# proiect2025_v16_sch.net
KiCad netlist of a schematic drawn in EAGLE
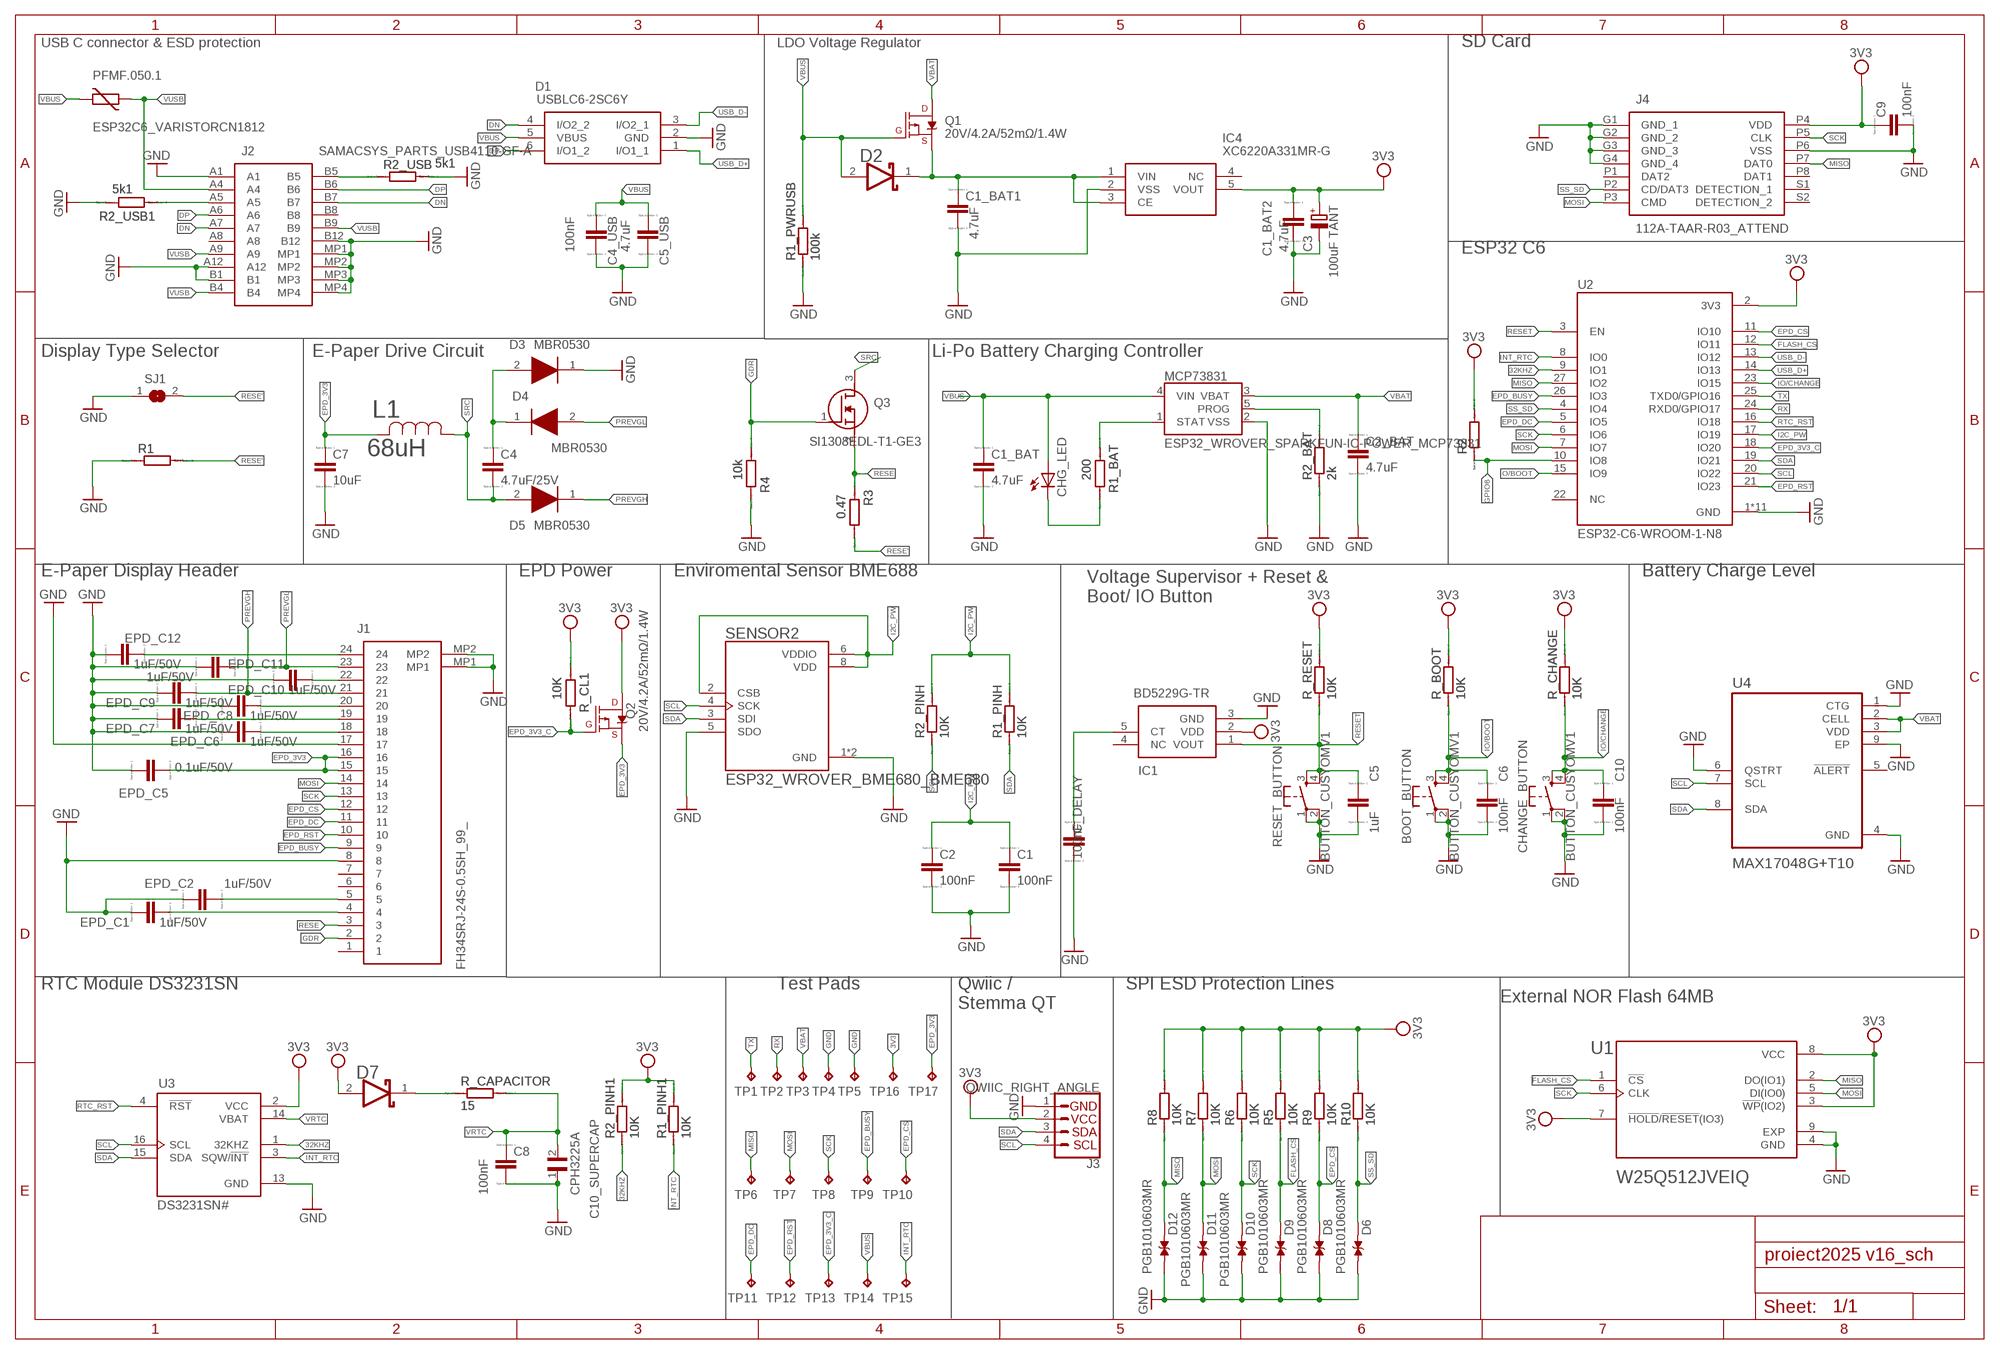
[diagram p0: schematic, sheet 1]

(export (version "E")
  (design (tool "Eeschema 10.0.6"))
  (components
    (comp (ref "BOOT_BUTTON")
      (value "BUTTON_CUSYOMV1")
      (footprint "eagle-import:MYBUTTON")
      (libsource (lib "eagle-import") (part "BUTTON_CUSYOMV1"))
    )
    (comp (ref "C1")
      (value "100nF")
      (footprint "eagle-import:EAGLE-LTSPICE_C0402")
      (libsource (lib "eagle-import") (part "EAGLE-LTSPICE_CC0402"))
    )
    (comp (ref "C1_BAT")
      (value "4.7uF")
      (footprint "eagle-import:EAGLE-LTSPICE_C0402")
      (libsource (lib "eagle-import") (part "EAGLE-LTSPICE_CC0402"))
    )
    (comp (ref "C1_BAT1")
      (value "4.7uF")
      (footprint "eagle-import:EAGLE-LTSPICE_C0402")
      (libsource (lib "eagle-import") (part "EAGLE-LTSPICE_CC0402"))
    )
    (comp (ref "C1_BAT2")
      (value "4.7uF")
      (footprint "eagle-import:EAGLE-LTSPICE_C0402")
      (libsource (lib "eagle-import") (part "EAGLE-LTSPICE_CC0402"))
    )
    (comp (ref "C2")
      (value "100nF")
      (footprint "eagle-import:EAGLE-LTSPICE_C0402")
      (libsource (lib "eagle-import") (part "EAGLE-LTSPICE_CC0402"))
    )
    (comp (ref "C2_BAT")
      (value "4.7uF")
      (footprint "eagle-import:EAGLE-LTSPICE_C0402")
      (libsource (lib "eagle-import") (part "EAGLE-LTSPICE_CC0402"))
    )
    (comp (ref "C3")
      (value "100uF TANT")
      (footprint "eagle-import:RCL_CT3528")
      (libsource (lib "eagle-import") (part "RCL_CPOL-EUCT3528"))
    )
    (comp (ref "C4")
      (value "4.7uF/25V")
      (footprint "eagle-import:EAGLE-LTSPICE_C0402")
      (libsource (lib "eagle-import") (part "EAGLE-LTSPICE_CC0402"))
    )
    (comp (ref "C4_USB")
      (value "100nF")
      (footprint "eagle-import:EAGLE-LTSPICE_C0402")
      (libsource (lib "eagle-import") (part "EAGLE-LTSPICE_CC0402"))
    )
    (comp (ref "C5")
      (value "1uF")
      (footprint "eagle-import:EAGLE-LTSPICE_C0402")
      (libsource (lib "eagle-import") (part "EAGLE-LTSPICE_CC0402"))
    )
    (comp (ref "C5_USB")
      (value "4.7uF")
      (footprint "eagle-import:EAGLE-LTSPICE_C0402")
      (libsource (lib "eagle-import") (part "EAGLE-LTSPICE_CC0402"))
    )
    (comp (ref "C6")
      (value "100nF")
      (footprint "eagle-import:EAGLE-LTSPICE_C0402")
      (libsource (lib "eagle-import") (part "EAGLE-LTSPICE_CC0402"))
    )
    (comp (ref "C7")
      (value "10uF")
      (footprint "eagle-import:EAGLE-LTSPICE_C0402")
      (libsource (lib "eagle-import") (part "EAGLE-LTSPICE_CC0402"))
    )
    (comp (ref "C8")
      (value "100nF")
      (footprint "eagle-import:EAGLE-LTSPICE_C0402")
      (libsource (lib "eagle-import") (part "EAGLE-LTSPICE_CC0402"))
    )
    (comp (ref "C9")
      (value "100nF")
      (footprint "eagle-import:EAGLE-LTSPICE_C0402")
      (libsource (lib "eagle-import") (part "EAGLE-LTSPICE_CC0402"))
    )
    (comp (ref "C10")
      (value "100nF")
      (footprint "eagle-import:EAGLE-LTSPICE_C0402")
      (libsource (lib "eagle-import") (part "EAGLE-LTSPICE_CC0402"))
    )
    (comp (ref "C10_SUPERCAP")
      (value "CPH3225A")
      (footprint "eagle-import:CAPCP3225X100N")
      (fields (field (name "MF") "Seiko Instruments"))
      (libsource (lib "eagle-import") (part "CPH3225A"))
    )
    (comp (ref "CHANGE_BUTTON")
      (value "BUTTON_CUSYOMV1")
      (footprint "eagle-import:MYBUTTON")
      (libsource (lib "eagle-import") (part "BUTTON_CUSYOMV1"))
    )
    (comp (ref "CHG_LED")
      (value "ADAFRUIT_LEDCHIP-LED0603")
      (footprint "eagle-import:ADAFRUIT_CHIP-LED0603")
      (libsource (lib "eagle-import") (part "ADAFRUIT_LEDCHIP-LED0603"))
    )
    (comp (ref "C_DELAY")
      (value "100nF")
      (footprint "eagle-import:EAGLE-LTSPICE_C0402")
      (libsource (lib "eagle-import") (part "EAGLE-LTSPICE_CC0402"))
    )
    (comp (ref "D1")
      (value "USBLC6-2SC6Y")
      (footprint "eagle-import:SOT95P280X145-6N")
      (fields (field (name "MF") "STMicroelectronics"))
      (libsource (lib "eagle-import") (part "USBLC6-2SC6Y"))
    )
    (comp (ref "D2")
      (value "ESP32_WROVER_AVX---SD0805S020S1R0_AVX_SD0805S020S1R0_0_0AVX_SD0805S020S1R0_0_0")
      (footprint "eagle-import:ESP32_WROVER_AVX---SD0805S020S1R0_AVX_SD0805S020S1R0_0")
      (fields
        (field (name "DIGIKEY_PART_NUMBER") "478-7800-1-ND")
        (field (name "MF") "AVX")
        (field (name "MOUSER_PART_NUMBER") "581-SD0805S020S1R0")
      )
      (libsource (lib "eagle-import") (part "ESP32_WROVER_AVX---SD0805S020S1R0_AVX_SD0805S020S1R0_0_0AVX_SD0805S020S1R0_0_0"))
    )
    (comp (ref "D3")
      (value "MBR0530")
      (footprint "eagle-import:SOD3716X135N")
      (fields (field (name "MF") "ON Semiconductor"))
      (libsource (lib "eagle-import") (part "MBR0530"))
    )
    (comp (ref "D4")
      (value "MBR0530")
      (footprint "eagle-import:SOD3716X135N")
      (fields (field (name "MF") "ON Semiconductor"))
      (libsource (lib "eagle-import") (part "MBR0530"))
    )
    (comp (ref "D5")
      (value "MBR0530")
      (footprint "eagle-import:SOD3716X135N")
      (fields (field (name "MF") "ON Semiconductor"))
      (libsource (lib "eagle-import") (part "MBR0530"))
    )
    (comp (ref "D6")
      (value "PGB1010603MR")
      (footprint "eagle-import:DIOC1608X36N")
      (fields (field (name "MF") "Littelfuse Inc."))
      (libsource (lib "eagle-import") (part "PGB1010603MR"))
    )
    (comp (ref "D7")
      (value "ESP32_WROVER_AVX---SD0805S020S1R0_AVX_SD0805S020S1R0_0_0AVX_SD0805S020S1R0_0_0")
      (footprint "eagle-import:ESP32_WROVER_AVX---SD0805S020S1R0_AVX_SD0805S020S1R0_0")
      (fields
        (field (name "DIGIKEY_PART_NUMBER") "478-7800-1-ND")
        (field (name "MF") "AVX")
        (field (name "MOUSER_PART_NUMBER") "581-SD0805S020S1R0")
      )
      (libsource (lib "eagle-import") (part "ESP32_WROVER_AVX---SD0805S020S1R0_AVX_SD0805S020S1R0_0_0AVX_SD0805S020S1R0_0_0"))
    )
    (comp (ref "D8")
      (value "PGB1010603MR")
      (footprint "eagle-import:DIOC1608X36N")
      (fields (field (name "MF") "Littelfuse Inc."))
      (libsource (lib "eagle-import") (part "PGB1010603MR"))
    )
    (comp (ref "D9")
      (value "PGB1010603MR")
      (footprint "eagle-import:DIOC1608X36N")
      (fields (field (name "MF") "Littelfuse Inc."))
      (libsource (lib "eagle-import") (part "PGB1010603MR"))
    )
    (comp (ref "D10")
      (value "PGB1010603MR")
      (footprint "eagle-import:DIOC1608X36N")
      (fields (field (name "MF") "Littelfuse Inc."))
      (libsource (lib "eagle-import") (part "PGB1010603MR"))
    )
    (comp (ref "D11")
      (value "PGB1010603MR")
      (footprint "eagle-import:DIOC1608X36N")
      (fields (field (name "MF") "Littelfuse Inc."))
      (libsource (lib "eagle-import") (part "PGB1010603MR"))
    )
    (comp (ref "D12")
      (value "PGB1010603MR")
      (footprint "eagle-import:DIOC1608X36N")
      (fields (field (name "MF") "Littelfuse Inc."))
      (libsource (lib "eagle-import") (part "PGB1010603MR"))
    )
    (comp (ref "EPD_C1")
      (value "1uF/50V")
      (footprint "eagle-import:EAGLE-LTSPICE_C0402")
      (libsource (lib "eagle-import") (part "EAGLE-LTSPICE_CC0402"))
    )
    (comp (ref "EPD_C2")
      (value "1uF/50V")
      (footprint "eagle-import:EAGLE-LTSPICE_C0402")
      (libsource (lib "eagle-import") (part "EAGLE-LTSPICE_CC0402"))
    )
    (comp (ref "EPD_C5")
      (value "0.1uF/50V")
      (footprint "eagle-import:EAGLE-LTSPICE_C0402")
      (libsource (lib "eagle-import") (part "EAGLE-LTSPICE_CC0402"))
    )
    (comp (ref "EPD_C6")
      (value "1uF/50V")
      (footprint "eagle-import:EAGLE-LTSPICE_C0402")
      (libsource (lib "eagle-import") (part "EAGLE-LTSPICE_CC0402"))
    )
    (comp (ref "EPD_C7")
      (value "1uF/50V")
      (footprint "eagle-import:EAGLE-LTSPICE_C0402")
      (libsource (lib "eagle-import") (part "EAGLE-LTSPICE_CC0402"))
    )
    (comp (ref "EPD_C8")
      (value "1uF/50V")
      (footprint "eagle-import:EAGLE-LTSPICE_C0402")
      (libsource (lib "eagle-import") (part "EAGLE-LTSPICE_CC0402"))
    )
    (comp (ref "EPD_C9")
      (value "1uF/50V")
      (footprint "eagle-import:EAGLE-LTSPICE_C0402")
      (libsource (lib "eagle-import") (part "EAGLE-LTSPICE_CC0402"))
    )
    (comp (ref "EPD_C10")
      (value "1uF/50V")
      (footprint "eagle-import:EAGLE-LTSPICE_C0402")
      (libsource (lib "eagle-import") (part "EAGLE-LTSPICE_CC0402"))
    )
    (comp (ref "EPD_C11")
      (value "1uF/50V")
      (footprint "eagle-import:EAGLE-LTSPICE_C0402")
      (libsource (lib "eagle-import") (part "EAGLE-LTSPICE_CC0402"))
    )
    (comp (ref "EPD_C12")
      (value "1uF/50V")
      (footprint "eagle-import:EAGLE-LTSPICE_C0402")
      (libsource (lib "eagle-import") (part "EAGLE-LTSPICE_CC0402"))
    )
    (comp (ref "IC1")
      (value "BD5229G-TR")
      (footprint "eagle-import:SOT95P280X125-5N")
      (fields (field (name "MOUSER_PART_NUMBER") "755-BD5229G-TR"))
      (libsource (lib "eagle-import") (part "BD5229G-TR"))
    )
    (comp (ref "IC4")
      (value "XC6220A331MR-G")
      (footprint "eagle-import:SOT95P280X120-5N")
      (fields (field (name "MOUSER_PART_NUMBER") "865-XC6220A331MR-G"))
      (libsource (lib "eagle-import") (part "XC6220A331MR-G"))
    )
    (comp (ref "J1")
      (value "FH34SRJ-24S-0.5SH_99_")
      (footprint "eagle-import:FH34SRJ24S05SH99")
      (fields
        (field (name "MANUFACTURER_PART_NUMBER") "FH34SRJ-24S-0.5SH(99)")
        (field (name "MOUSER_PART_NUMBER") "798-FH34SRJ24S05SH99")
      )
      (libsource (lib "eagle-import") (part "FH34SRJ-24S-0.5SH_99_"))
    )
    (comp (ref "J2")
      (value "SAMACSYS_PARTS_USB4110-GF-A")
      (footprint "eagle-import:SAMACSYS_PARTS_USB4110GFA")
      (fields
        (field (name "MANUFACTURER_PART_NUMBER") "USB4110-GF-A")
        (field (name "MOUSER_PART_NUMBER") "640-USB4110-GF-A")
      )
      (libsource (lib "eagle-import") (part "SAMACSYS_PARTS_USB4110-GF-A"))
    )
    (comp (ref "J3")
      (value "QWIIC_RIGHT_ANGLE")
      (footprint "eagle-import:JST04_1MM_RA")
      (libsource (lib "eagle-import") (part "QWIIC_CONNECTORJS-1MM"))
    )
    (comp (ref "J4")
      (value "112A-TAAR-R03_ATTEND")
      (footprint "eagle-import:112ATAARR03ATTEND")
      (fields (field (name "MANUFACTURER_PART_NUMBER") "112A-TAAR-R03 ATTEND"))
      (libsource (lib "eagle-import") (part "112A-TAAR-R03_ATTEND"))
    )
    (comp (ref "L1")
      (value "68uH")
      (footprint "eagle-import:IND_4828-WE-TPC_WRE")
      (fields
        (field (name "MANUFACTURER_PART_NUMBER") "744043680")
        (field (name "COPYRIGHT") "Copyright (C) 2024 Ultra Librarian. All rights reserved.")
      )
      (libsource (lib "eagle-import") (part "744043680IND_4828-WE-TPC_WRE"))
    )
    (comp (ref "MCP73831")
      (value "ESP32_WROVER_SPARKFUN-IC-POWER_MCP73831")
      (footprint "eagle-import:ESP32_WROVER_SPARKFUN-IC-POWER_SOT23-5")
      (libsource (lib "eagle-import") (part "ESP32_WROVER_SPARKFUN-IC-POWER_MCP73831"))
    )
    (comp (ref "PFMF.050.1")
      (value "ESP32C6_VARISTORCN1812")
      (footprint "eagle-import:ESP32C6_VARISTOR_CT_CN1812")
      (libsource (lib "eagle-import") (part "ESP32C6_VARISTORCN1812"))
    )
    (comp (ref "Q1")
      (value "20V/4.2A/52mΩ/1.4W")
      (footprint "eagle-import:ESP32_WROVER_SPARKFUN-DISCRETESEMI_SOT23-3")
      (libsource (lib "eagle-import") (part "ESP32_WROVER_SPARKFUN-DISCRETESEMI_MOSFET_PCH-DMG2305UX-7"))
    )
    (comp (ref "Q2")
      (value "20V/4.2A/52mΩ/1.4W")
      (footprint "eagle-import:ESP32_WROVER_SPARKFUN-DISCRETESEMI_SOT23-3")
      (libsource (lib "eagle-import") (part "ESP32_WROVER_SPARKFUN-DISCRETESEMI_MOSFET_PCH-DMG2305UX-7"))
    )
    (comp (ref "Q3")
      (value "SI1308EDL-T1-GE3")
      (footprint "eagle-import:SOT65P210X110-3N")
      (fields (field (name "MF") "Vishay Siliconix"))
      (libsource (lib "eagle-import") (part "SI1308EDL-T1-GE3"))
    )
    (comp (ref "R1")
      (value "ESP32_WROVER_EAGLE-LTSPICE_RR0402")
      (footprint "eagle-import:ESP32_WROVER_EAGLE-LTSPICE_R0402")
      (libsource (lib "eagle-import") (part "ESP32_WROVER_EAGLE-LTSPICE_RR0402"))
    )
    (comp (ref "R1_BAT")
      (value "200")
      (footprint "eagle-import:ESP32_WROVER_EAGLE-LTSPICE_R0402")
      (libsource (lib "eagle-import") (part "ESP32_WROVER_EAGLE-LTSPICE_RR0402"))
    )
    (comp (ref "R1_PINH")
      (value "10K")
      (footprint "eagle-import:ESP32_WROVER_EAGLE-LTSPICE_R0402")
      (libsource (lib "eagle-import") (part "ESP32_WROVER_EAGLE-LTSPICE_RR0402"))
    )
    (comp (ref "R1_PINH1")
      (value "10K")
      (footprint "eagle-import:ESP32_WROVER_EAGLE-LTSPICE_R0402")
      (libsource (lib "eagle-import") (part "ESP32_WROVER_EAGLE-LTSPICE_RR0402"))
    )
    (comp (ref "R1_PWRUSB")
      (value "100k")
      (footprint "eagle-import:ESP32_WROVER_EAGLE-LTSPICE_R0402")
      (libsource (lib "eagle-import") (part "ESP32_WROVER_EAGLE-LTSPICE_RR0402"))
    )
    (comp (ref "R2")
      (value "ESP32_WROVER_EAGLE-LTSPICE_RR0402")
      (footprint "eagle-import:ESP32_WROVER_EAGLE-LTSPICE_R0402")
      (libsource (lib "eagle-import") (part "ESP32_WROVER_EAGLE-LTSPICE_RR0402"))
    )
    (comp (ref "R2_BAT")
      (value "2k")
      (footprint "eagle-import:ESP32_WROVER_EAGLE-LTSPICE_R0402")
      (libsource (lib "eagle-import") (part "ESP32_WROVER_EAGLE-LTSPICE_RR0402"))
    )
    (comp (ref "R2_PINH")
      (value "10K")
      (footprint "eagle-import:ESP32_WROVER_EAGLE-LTSPICE_R0402")
      (libsource (lib "eagle-import") (part "ESP32_WROVER_EAGLE-LTSPICE_RR0402"))
    )
    (comp (ref "R2_PINH1")
      (value "10K")
      (footprint "eagle-import:ESP32_WROVER_EAGLE-LTSPICE_R0402")
      (libsource (lib "eagle-import") (part "ESP32_WROVER_EAGLE-LTSPICE_RR0402"))
    )
    (comp (ref "R2_USB")
      (value "5k1")
      (footprint "eagle-import:ESP32_WROVER_EAGLE-LTSPICE_R0402")
      (libsource (lib "eagle-import") (part "ESP32_WROVER_EAGLE-LTSPICE_RR0402"))
    )
    (comp (ref "R2_USB1")
      (value "5k1")
      (footprint "eagle-import:ESP32_WROVER_EAGLE-LTSPICE_R0402")
      (libsource (lib "eagle-import") (part "ESP32_WROVER_EAGLE-LTSPICE_RR0402"))
    )
    (comp (ref "R3")
      (value "0.47")
      (footprint "eagle-import:ESP32_WROVER_EAGLE-LTSPICE_R0402")
      (libsource (lib "eagle-import") (part "ESP32_WROVER_EAGLE-LTSPICE_RR0402"))
    )
    (comp (ref "R4")
      (value "10k")
      (footprint "eagle-import:ESP32_WROVER_EAGLE-LTSPICE_R0402")
      (libsource (lib "eagle-import") (part "ESP32_WROVER_EAGLE-LTSPICE_RR0402"))
    )
    (comp (ref "R5")
      (value "10K")
      (footprint "eagle-import:ESP32_WROVER_EAGLE-LTSPICE_R0402")
      (libsource (lib "eagle-import") (part "ESP32_WROVER_EAGLE-LTSPICE_RR0402"))
    )
    (comp (ref "R6")
      (value "10K")
      (footprint "eagle-import:ESP32_WROVER_EAGLE-LTSPICE_R0402")
      (libsource (lib "eagle-import") (part "ESP32_WROVER_EAGLE-LTSPICE_RR0402"))
    )
    (comp (ref "R7")
      (value "10K")
      (footprint "eagle-import:ESP32_WROVER_EAGLE-LTSPICE_R0402")
      (libsource (lib "eagle-import") (part "ESP32_WROVER_EAGLE-LTSPICE_RR0402"))
    )
    (comp (ref "R8")
      (value "10K")
      (footprint "eagle-import:ESP32_WROVER_EAGLE-LTSPICE_R0402")
      (libsource (lib "eagle-import") (part "ESP32_WROVER_EAGLE-LTSPICE_RR0402"))
    )
    (comp (ref "R9")
      (value "10K")
      (footprint "eagle-import:ESP32_WROVER_EAGLE-LTSPICE_R0402")
      (libsource (lib "eagle-import") (part "ESP32_WROVER_EAGLE-LTSPICE_RR0402"))
    )
    (comp (ref "R10")
      (value "10K")
      (footprint "eagle-import:ESP32_WROVER_EAGLE-LTSPICE_R0402")
      (libsource (lib "eagle-import") (part "ESP32_WROVER_EAGLE-LTSPICE_RR0402"))
    )
    (comp (ref "RESET_BUTTON")
      (value "BUTTON_CUSYOMV1")
      (footprint "eagle-import:MYBUTTON")
      (libsource (lib "eagle-import") (part "BUTTON_CUSYOMV1"))
    )
    (comp (ref "R_BOOT")
      (value "10K")
      (footprint "eagle-import:ESP32_WROVER_EAGLE-LTSPICE_R0402")
      (libsource (lib "eagle-import") (part "ESP32_WROVER_EAGLE-LTSPICE_RR0402"))
    )
    (comp (ref "R_CAPACITOR")
      (value "15")
      (footprint "eagle-import:ESP32_WROVER_EAGLE-LTSPICE_R0402")
      (libsource (lib "eagle-import") (part "ESP32_WROVER_EAGLE-LTSPICE_RR0402"))
    )
    (comp (ref "R_CHANGE")
      (value "10K")
      (footprint "eagle-import:ESP32_WROVER_EAGLE-LTSPICE_R0402")
      (libsource (lib "eagle-import") (part "ESP32_WROVER_EAGLE-LTSPICE_RR0402"))
    )
    (comp (ref "R_CL1")
      (value "10K")
      (footprint "eagle-import:ESP32_WROVER_EAGLE-LTSPICE_R0402")
      (libsource (lib "eagle-import") (part "ESP32_WROVER_EAGLE-LTSPICE_RR0402"))
    )
    (comp (ref "R_RESET")
      (value "10K")
      (footprint "eagle-import:ESP32_WROVER_EAGLE-LTSPICE_R0402")
      (libsource (lib "eagle-import") (part "ESP32_WROVER_EAGLE-LTSPICE_RR0402"))
    )
    (comp (ref "SENSOR2")
      (value "ESP32_WROVER_BME680_BME680")
      (footprint "eagle-import:ESP32_WROVER_BME680_PSON80P300X300X100-8N")
      (fields (field (name "MF") "Bosch Sensortec") (field (name "MP") "BME680"))
      (libsource (lib "eagle-import") (part "ESP32_WROVER_BME680_BME680"))
    )
    (comp (ref "SJ1") (value "SJ") (footprint "eagle-import:SJ") (libsource (lib "eagle-import") (part "SJ")))
    (comp (ref "TP1")
      (value "TPTP20R")
      (footprint "eagle-import:TP20R")
      (libsource (lib "eagle-import") (part "TPTP20R"))
    )
    (comp (ref "TP2")
      (value "TPTP20R")
      (footprint "eagle-import:TP20R")
      (libsource (lib "eagle-import") (part "TPTP20R"))
    )
    (comp (ref "TP3")
      (value "TPTP20R")
      (footprint "eagle-import:TP20R")
      (libsource (lib "eagle-import") (part "TPTP20R"))
    )
    (comp (ref "TP4")
      (value "TPTP20R")
      (footprint "eagle-import:TP20R")
      (libsource (lib "eagle-import") (part "TPTP20R"))
    )
    (comp (ref "TP5")
      (value "TPTP20R")
      (footprint "eagle-import:TP20R")
      (libsource (lib "eagle-import") (part "TPTP20R"))
    )
    (comp (ref "TP6")
      (value "TPTP20R")
      (footprint "eagle-import:TP20R")
      (libsource (lib "eagle-import") (part "TPTP20R"))
    )
    (comp (ref "TP7")
      (value "TPTP20R")
      (footprint "eagle-import:TP20R")
      (libsource (lib "eagle-import") (part "TPTP20R"))
    )
    (comp (ref "TP8")
      (value "TPTP20R")
      (footprint "eagle-import:TP20R")
      (libsource (lib "eagle-import") (part "TPTP20R"))
    )
    (comp (ref "TP9")
      (value "TPTP20R")
      (footprint "eagle-import:TP20R")
      (libsource (lib "eagle-import") (part "TPTP20R"))
    )
    (comp (ref "TP10")
      (value "TPTP20R")
      (footprint "eagle-import:TP20R")
      (libsource (lib "eagle-import") (part "TPTP20R"))
    )
    (comp (ref "TP11")
      (value "TPTP20R")
      (footprint "eagle-import:TP20R")
      (libsource (lib "eagle-import") (part "TPTP20R"))
    )
    (comp (ref "TP12")
      (value "TPTP20R")
      (footprint "eagle-import:TP20R")
      (libsource (lib "eagle-import") (part "TPTP20R"))
    )
    (comp (ref "TP13")
      (value "TPTP20R")
      (footprint "eagle-import:TP20R")
      (libsource (lib "eagle-import") (part "TPTP20R"))
    )
    (comp (ref "TP14")
      (value "TPTP20R")
      (footprint "eagle-import:TP20R")
      (libsource (lib "eagle-import") (part "TPTP20R"))
    )
    (comp (ref "TP15")
      (value "TPTP20R")
      (footprint "eagle-import:TP20R")
      (libsource (lib "eagle-import") (part "TPTP20R"))
    )
    (comp (ref "TP16")
      (value "TPTP20R")
      (footprint "eagle-import:TP20R")
      (libsource (lib "eagle-import") (part "TPTP20R"))
    )
    (comp (ref "TP17")
      (value "TPTP20R")
      (footprint "eagle-import:TP20R")
      (libsource (lib "eagle-import") (part "TPTP20R"))
    )
    (comp (ref "U1")
      (value "W25Q512JVEIQ")
      (footprint "eagle-import:SON127P600X800X80-9N")
      (fields (field (name "MF") "Winbond Electronics"))
      (libsource (lib "eagle-import") (part "W25Q512JVEIQ"))
    )
    (comp (ref "U2")
      (value "ESP32-C6-WROOM-1-N8")
      (footprint "eagle-import:XCVR_ESP32-C6-WROOM-1-N8")
      (fields (field (name "MF") "Espressif Systems"))
      (libsource (lib "eagle-import") (part "ESP32-C6-WROOM-1-N8"))
    )
    (comp (ref "U3")
      (value "DS3231SN#")
      (footprint "eagle-import:SOIC127P1032X265-16N")
      (fields (field (name "MF") "Analog Devices"))
      (libsource (lib "eagle-import") (part "DS3231SN#"))
    )
    (comp (ref "U4")
      (value "MAX17048G+T10")
      (footprint "eagle-import:SON50P200X200X80-9N")
      (fields (field (name "MF") "Analog Devices"))
      (libsource (lib "eagle-import") (part "MAX17048G+T10"))
    )
  )
  (nets
    (net (code "1") (name "3V3") (class "Default")
      (node (ref "C1_BAT2") (pin "1") (pinfunction "1_1") (pintype "passive"))
      (node (ref "C3") (pin "+") (pinfunction "+_+") (pintype "passive"))
      (node (ref "C9") (pin "1") (pinfunction "1_1") (pintype "passive"))
      (node (ref "D7") (pin "2") (pinfunction "ANODE_2") (pintype "bidirectional"))
      (node (ref "IC1") (pin "2") (pinfunction "VDD_2") (pintype "bidirectional"))
      (node (ref "IC4") (pin "5") (pinfunction "VOUT_5") (pintype "bidirectional"))
      (node (ref "J3") (pin "2") (pinfunction "2_2") (pintype "power_in"))
      (node (ref "J4") (pin "P4") (pinfunction "VDD_P4") (pintype "bidirectional"))
      (node (ref "Q2") (pin "3") (pinfunction "D_3") (pintype "bidirectional"))
      (node (ref "R10") (pin "2") (pinfunction "2_2") (pintype "passive"))
      (node (ref "R1_PINH1") (pin "2") (pinfunction "2_2") (pintype "passive"))
      (node (ref "R2") (pin "2") (pinfunction "2_2") (pintype "passive"))
      (node (ref "R2_PINH1") (pin "2") (pinfunction "2_2") (pintype "passive"))
      (node (ref "R5") (pin "2") (pinfunction "2_2") (pintype "passive"))
      (node (ref "R6") (pin "2") (pinfunction "2_2") (pintype "passive"))
      (node (ref "R7") (pin "2") (pinfunction "2_2") (pintype "passive"))
      (node (ref "R8") (pin "2") (pinfunction "2_2") (pintype "passive"))
      (node (ref "R9") (pin "2") (pinfunction "2_2") (pintype "passive"))
      (node (ref "R_BOOT") (pin "2") (pinfunction "2_2") (pintype "passive"))
      (node (ref "R_CHANGE") (pin "2") (pinfunction "2_2") (pintype "passive"))
      (node (ref "R_CL1") (pin "2") (pinfunction "2_2") (pintype "passive"))
      (node (ref "R_RESET") (pin "2") (pinfunction "2_2") (pintype "passive"))
      (node (ref "TP16") (pin "TP") (pinfunction "TP_TP") (pintype "input"))
      (node (ref "U1") (pin "3") (pinfunction "~{WP}(IO2)_3") (pintype "bidirectional"))
      (node (ref "U1") (pin "7") (pinfunction "~{HOLD}/~{RESET}(IO3)_7") (pintype "bidirectional"))
      (node (ref "U1") (pin "8") (pinfunction "VCC_8") (pintype "power_in"))
      (node (ref "U2") (pin "2") (pinfunction "3V3_2") (pintype "power_in"))
      (node (ref "U3") (pin "2") (pinfunction "VCC_2") (pintype "power_in"))
    )
    (net (code "2") (name "32KHZ") (class "Default")
      (node (ref "R2_PINH1") (pin "1") (pinfunction "1_1") (pintype "passive"))
      (node (ref "U2") (pin "9") (pinfunction "IO1_9") (pintype "bidirectional"))
      (node (ref "U3") (pin "1") (pinfunction "32KHZ_1") (pintype "output"))
    )
    (net (code "3") (name "DN") (class "Default")
      (node (ref "D1") (pin "4") (pinfunction "I/O2_2_4") (pintype "bidirectional"))
      (node (ref "J2") (pin "A7") (pinfunction "A7_A7") (pintype "bidirectional"))
      (node (ref "J2") (pin "B7") (pinfunction "B7_B7") (pintype "bidirectional"))
    )
    (net (code "4") (name "DP") (class "Default")
      (node (ref "D1") (pin "6") (pinfunction "I/O1_2_6") (pintype "bidirectional"))
      (node (ref "J2") (pin "A6") (pinfunction "A6_A6") (pintype "bidirectional"))
      (node (ref "J2") (pin "B6") (pinfunction "B6_B6") (pintype "bidirectional"))
    )
    (net (code "5") (name "EPD_3V3") (class "Default")
      (node (ref "C7") (pin "1") (pinfunction "1_1") (pintype "passive"))
      (node (ref "EPD_C5") (pin "2") (pinfunction "2_2") (pintype "passive"))
      (node (ref "J1") (pin "15") (pinfunction "15_15") (pintype "bidirectional"))
      (node (ref "J1") (pin "16") (pinfunction "16_16") (pintype "bidirectional"))
      (node (ref "L1") (pin "2") (pinfunction "2_2") (pintype "passive"))
      (node (ref "Q2") (pin "2") (pinfunction "S_2") (pintype "bidirectional"))
      (node (ref "TP17") (pin "TP") (pinfunction "TP_TP") (pintype "input"))
    )
    (net (code "6") (name "EPD_3V3_C") (class "Default")
      (node (ref "Q2") (pin "1") (pinfunction "G_1") (pintype "bidirectional"))
      (node (ref "R_CL1") (pin "1") (pinfunction "1_1") (pintype "passive"))
      (node (ref "TP13") (pin "TP") (pinfunction "TP_TP") (pintype "input"))
      (node (ref "U2") (pin "18") (pinfunction "IO20_18") (pintype "bidirectional"))
    )
    (net (code "7") (name "EPD_BUSY") (class "Default")
      (node (ref "J1") (pin "9") (pinfunction "9_9") (pintype "bidirectional"))
      (node (ref "TP9") (pin "TP") (pinfunction "TP_TP") (pintype "input"))
      (node (ref "U2") (pin "26") (pinfunction "IO3_26") (pintype "bidirectional"))
    )
    (net (code "8") (name "EPD_CS") (class "Default")
      (node (ref "D8") (pin "2") (pinfunction "2_2") (pintype "passive"))
      (node (ref "J1") (pin "12") (pinfunction "12_12") (pintype "bidirectional"))
      (node (ref "R9") (pin "1") (pinfunction "1_1") (pintype "passive"))
      (node (ref "TP10") (pin "TP") (pinfunction "TP_TP") (pintype "input"))
      (node (ref "U2") (pin "11") (pinfunction "IO10_11") (pintype "bidirectional"))
    )
    (net (code "9") (name "EPD_DC") (class "Default")
      (node (ref "J1") (pin "11") (pinfunction "11_11") (pintype "bidirectional"))
      (node (ref "TP11") (pin "TP") (pinfunction "TP_TP") (pintype "input"))
      (node (ref "U2") (pin "5") (pinfunction "IO5_5") (pintype "bidirectional"))
    )
    (net (code "10") (name "EPD_RST") (class "Default")
      (node (ref "J1") (pin "10") (pinfunction "10_10") (pintype "bidirectional"))
      (node (ref "TP12") (pin "TP") (pinfunction "TP_TP") (pintype "input"))
      (node (ref "U2") (pin "21") (pinfunction "IO23_21") (pintype "bidirectional"))
    )
    (net (code "11") (name "FLASH_CS") (class "Default")
      (node (ref "D9") (pin "2") (pinfunction "2_2") (pintype "passive"))
      (node (ref "R5") (pin "1") (pinfunction "1_1") (pintype "passive"))
      (node (ref "U1") (pin "1") (pinfunction "~{CS}_1") (pintype "input"))
      (node (ref "U2") (pin "12") (pinfunction "IO11_12") (pintype "bidirectional"))
    )
    (net (code "12") (name "GDR") (class "Default")
      (node (ref "J1") (pin "2") (pinfunction "2_2") (pintype "bidirectional"))
      (node (ref "Q3") (pin "1") (pinfunction "G_1") (pintype "bidirectional"))
      (node (ref "R4") (pin "2") (pinfunction "2_2") (pintype "passive"))
    )
    (net (code "13") (name "GND") (class "Default")
      (node (ref "BOOT_BUTTON") (pin "1") (pinfunction "1_1") (pintype "passive"))
      (node (ref "BOOT_BUTTON") (pin "2") (pinfunction "2_2") (pintype "passive"))
      (node (ref "C1") (pin "2") (pinfunction "2_2") (pintype "passive"))
      (node (ref "C10") (pin "2") (pinfunction "2_2") (pintype "passive"))
      (node (ref "C10_SUPERCAP") (pin "1") (pinfunction "1_1") (pintype "passive"))
      (node (ref "C1_BAT") (pin "2") (pinfunction "2_2") (pintype "passive"))
      (node (ref "C1_BAT1") (pin "2") (pinfunction "2_2") (pintype "passive"))
      (node (ref "C1_BAT2") (pin "2") (pinfunction "2_2") (pintype "passive"))
      (node (ref "C2") (pin "2") (pinfunction "2_2") (pintype "passive"))
      (node (ref "C2_BAT") (pin "2") (pinfunction "2_2") (pintype "passive"))
      (node (ref "C3") (pin "-") (pinfunction "-_-") (pintype "passive"))
      (node (ref "C4_USB") (pin "2") (pinfunction "2_2") (pintype "passive"))
      (node (ref "C5") (pin "2") (pinfunction "2_2") (pintype "passive"))
      (node (ref "C5_USB") (pin "2") (pinfunction "2_2") (pintype "passive"))
      (node (ref "C6") (pin "2") (pinfunction "2_2") (pintype "passive"))
      (node (ref "C7") (pin "2") (pinfunction "2_2") (pintype "passive"))
      (node (ref "C8") (pin "2") (pinfunction "2_2") (pintype "passive"))
      (node (ref "C9") (pin "2") (pinfunction "2_2") (pintype "passive"))
      (node (ref "CHANGE_BUTTON") (pin "1") (pinfunction "1_1") (pintype "passive"))
      (node (ref "CHANGE_BUTTON") (pin "2") (pinfunction "2_2") (pintype "passive"))
      (node (ref "C_DELAY") (pin "2") (pinfunction "2_2") (pintype "passive"))
      (node (ref "D1") (pin "2") (pinfunction "GND_2") (pintype "bidirectional"))
      (node (ref "D10") (pin "1") (pinfunction "1_1") (pintype "passive"))
      (node (ref "D11") (pin "1") (pinfunction "1_1") (pintype "passive"))
      (node (ref "D12") (pin "1") (pinfunction "1_1") (pintype "passive"))
      (node (ref "D3") (pin "1") (pinfunction "K_1") (pintype "bidirectional"))
      (node (ref "D6") (pin "1") (pinfunction "1_1") (pintype "passive"))
      (node (ref "D8") (pin "1") (pinfunction "1_1") (pintype "passive"))
      (node (ref "D9") (pin "1") (pinfunction "1_1") (pintype "passive"))
      (node (ref "EPD_C1") (pin "1") (pinfunction "1_1") (pintype "passive"))
      (node (ref "EPD_C10") (pin "1") (pinfunction "1_1") (pintype "passive"))
      (node (ref "EPD_C11") (pin "1") (pinfunction "1_1") (pintype "passive"))
      (node (ref "EPD_C12") (pin "1") (pinfunction "1_1") (pintype "passive"))
      (node (ref "EPD_C2") (pin "1") (pinfunction "1_1") (pintype "passive"))
      (node (ref "EPD_C5") (pin "1") (pinfunction "1_1") (pintype "passive"))
      (node (ref "EPD_C6") (pin "1") (pinfunction "1_1") (pintype "passive"))
      (node (ref "EPD_C7") (pin "1") (pinfunction "1_1") (pintype "passive"))
      (node (ref "EPD_C8") (pin "1") (pinfunction "1_1") (pintype "passive"))
      (node (ref "EPD_C9") (pin "1") (pinfunction "1_1") (pintype "passive"))
      (node (ref "IC1") (pin "3") (pinfunction "GND_3") (pintype "bidirectional"))
      (node (ref "IC4") (pin "2") (pinfunction "VSS_2") (pintype "bidirectional"))
      (node (ref "J1") (pin "17") (pinfunction "17_17") (pintype "bidirectional"))
      (node (ref "J1") (pin "8") (pinfunction "8_8") (pintype "bidirectional"))
      (node (ref "J1") (pin "MP1") (pinfunction "MP1_MP1") (pintype "bidirectional"))
      (node (ref "J1") (pin "MP2") (pinfunction "MP2_MP2") (pintype "bidirectional"))
      (node (ref "J2") (pin "A1") (pinfunction "A1_A1") (pintype "bidirectional"))
      (node (ref "J2") (pin "A12") (pinfunction "A12_A12") (pintype "bidirectional"))
      (node (ref "J2") (pin "B1") (pinfunction "B1_B1") (pintype "bidirectional"))
      (node (ref "J2") (pin "B12") (pinfunction "B12_B12") (pintype "bidirectional"))
      (node (ref "J2") (pin "MP1") (pinfunction "MP1_MP1") (pintype "bidirectional"))
      (node (ref "J2") (pin "MP2") (pinfunction "MP2_MP2") (pintype "bidirectional"))
      (node (ref "J2") (pin "MP3") (pinfunction "MP3_MP3") (pintype "bidirectional"))
      (node (ref "J2") (pin "MP4") (pinfunction "MP4_MP4") (pintype "bidirectional"))
      (node (ref "J3") (pin "1") (pinfunction "1_1") (pintype "power_in"))
      (node (ref "J4") (pin "G1") (pinfunction "GND_1_G1") (pintype "bidirectional"))
      (node (ref "J4") (pin "G2") (pinfunction "GND_2_G2") (pintype "bidirectional"))
      (node (ref "J4") (pin "G3") (pinfunction "GND_3_G3") (pintype "bidirectional"))
      (node (ref "J4") (pin "G4") (pinfunction "GND_4_G4") (pintype "bidirectional"))
      (node (ref "J4") (pin "P6") (pinfunction "VSS_P6") (pintype "bidirectional"))
      (node (ref "MCP73831") (pin "2") (pinfunction "VSS_2") (pintype "power_in"))
      (node (ref "R1") (pin "1") (pinfunction "1_1") (pintype "passive"))
      (node (ref "R1_PWRUSB") (pin "1") (pinfunction "1_1") (pintype "passive"))
      (node (ref "R2_BAT") (pin "1") (pinfunction "1_1") (pintype "passive"))
      (node (ref "R2_USB") (pin "2") (pinfunction "2_2") (pintype "passive"))
      (node (ref "R2_USB1") (pin "1") (pinfunction "1_1") (pintype "passive"))
      (node (ref "R4") (pin "1") (pinfunction "1_1") (pintype "passive"))
      (node (ref "RESET_BUTTON") (pin "1") (pinfunction "1_1") (pintype "passive"))
      (node (ref "RESET_BUTTON") (pin "2") (pinfunction "2_2") (pintype "passive"))
      (node (ref "SENSOR2") (pin "1") (pinfunction "GND_1") (pintype "power_in"))
      (node (ref "SENSOR2") (pin "5") (pinfunction "SDO_5") (pintype "bidirectional"))
      (node (ref "SENSOR2") (pin "7") (pinfunction "GND_7") (pintype "power_in"))
      (node (ref "SJ1") (pin "1") (pinfunction "1_1") (pintype "passive"))
      (node (ref "TP4") (pin "TP") (pinfunction "TP_TP") (pintype "input"))
      (node (ref "TP5") (pin "TP") (pinfunction "TP_TP") (pintype "input"))
      (node (ref "U1") (pin "4") (pinfunction "GND_4") (pintype "power_in"))
      (node (ref "U1") (pin "9") (pinfunction "EXP_9") (pintype "passive"))
      (node (ref "U2") (pin "1") (pinfunction "GND_1") (pintype "power_in"))
      (node (ref "U2") (pin "28") (pinfunction "GND_28") (pintype "power_in"))
      (node (ref "U2") (pin "29_1") (pinfunction "GND_29_1") (pintype "power_in"))
      (node (ref "U2") (pin "29_2") (pinfunction "GND_29_2") (pintype "power_in"))
      (node (ref "U2") (pin "29_3") (pinfunction "GND_29_3") (pintype "power_in"))
      (node (ref "U2") (pin "29_4") (pinfunction "GND_29_4") (pintype "power_in"))
      (node (ref "U2") (pin "29_5") (pinfunction "GND_29_5") (pintype "power_in"))
      (node (ref "U2") (pin "29_6") (pinfunction "GND_29_6") (pintype "power_in"))
      (node (ref "U2") (pin "29_7") (pinfunction "GND_29_7") (pintype "power_in"))
      (node (ref "U2") (pin "29_8") (pinfunction "GND_29_8") (pintype "power_in"))
      (node (ref "U2") (pin "29_9") (pinfunction "GND_29_9") (pintype "power_in"))
      (node (ref "U3") (pin "13") (pinfunction "GND_13") (pintype "power_in"))
      (node (ref "U4") (pin "1") (pinfunction "CTG_1") (pintype "power_in"))
      (node (ref "U4") (pin "4") (pinfunction "GND_4") (pintype "power_in"))
      (node (ref "U4") (pin "6") (pinfunction "QSTRT_6") (pintype "input"))
      (node (ref "U4") (pin "9") (pinfunction "EP_9") (pintype "power_in"))
    )
    (net (code "14") (name "GPIO8") (class "Default")
      (node (ref "R2") (pin "1") (pinfunction "1_1") (pintype "passive"))
      (node (ref "U2") (pin "10") (pinfunction "IO8_10") (pintype "bidirectional"))
    )
    (net (code "15") (name "I2C_PW") (class "Default")
      (node (ref "C1") (pin "1") (pinfunction "1_1") (pintype "passive"))
      (node (ref "C2") (pin "1") (pinfunction "1_1") (pintype "passive"))
      (node (ref "R1_PINH") (pin "2") (pinfunction "2_2") (pintype "passive"))
      (node (ref "R2_PINH") (pin "2") (pinfunction "2_2") (pintype "passive"))
      (node (ref "SENSOR2") (pin "2") (pinfunction "CSB_2") (pintype "input"))
      (node (ref "SENSOR2") (pin "6") (pinfunction "VDDIO_6") (pintype "power_in"))
      (node (ref "SENSOR2") (pin "8") (pinfunction "VDD_8") (pintype "power_in"))
      (node (ref "U2") (pin "17") (pinfunction "IO19_17") (pintype "bidirectional"))
    )
    (net (code "16") (name "INT_RTC") (class "Default")
      (node (ref "R1_PINH1") (pin "1") (pinfunction "1_1") (pintype "passive"))
      (node (ref "TP15") (pin "TP") (pinfunction "TP_TP") (pintype "input"))
      (node (ref "U2") (pin "8") (pinfunction "IO0_8") (pintype "bidirectional"))
      (node (ref "U3") (pin "3") (pinfunction "SQW/~{INT}_3") (pintype "output"))
    )
    (net (code "17") (name "IO{slash}BOOT") (class "Default")
      (node (ref "BOOT_BUTTON") (pin "3") (pinfunction "3_3") (pintype "passive"))
      (node (ref "BOOT_BUTTON") (pin "4") (pinfunction "4_4") (pintype "passive"))
      (node (ref "C6") (pin "1") (pinfunction "1_1") (pintype "passive"))
      (node (ref "R_BOOT") (pin "1") (pinfunction "1_1") (pintype "passive"))
      (node (ref "U2") (pin "15") (pinfunction "IO9_15") (pintype "bidirectional"))
    )
    (net (code "18") (name "IO{slash}CHANGE") (class "Default")
      (node (ref "C10") (pin "1") (pinfunction "1_1") (pintype "passive"))
      (node (ref "CHANGE_BUTTON") (pin "3") (pinfunction "3_3") (pintype "passive"))
      (node (ref "CHANGE_BUTTON") (pin "4") (pinfunction "4_4") (pintype "passive"))
      (node (ref "R_CHANGE") (pin "1") (pinfunction "1_1") (pintype "passive"))
      (node (ref "U2") (pin "23") (pinfunction "IO15_23") (pintype "bidirectional"))
    )
    (net (code "19") (name "MISO") (class "Default")
      (node (ref "D12") (pin "2") (pinfunction "2_2") (pintype "passive"))
      (node (ref "J4") (pin "P7") (pinfunction "DAT0_P7") (pintype "bidirectional"))
      (node (ref "R8") (pin "1") (pinfunction "1_1") (pintype "passive"))
      (node (ref "TP6") (pin "TP") (pinfunction "TP_TP") (pintype "input"))
      (node (ref "U1") (pin "2") (pinfunction "DO(IO1)_2") (pintype "bidirectional"))
      (node (ref "U2") (pin "27") (pinfunction "IO2_27") (pintype "bidirectional"))
    )
    (net (code "20") (name "MOSI") (class "Default")
      (node (ref "D11") (pin "2") (pinfunction "2_2") (pintype "passive"))
      (node (ref "J1") (pin "14") (pinfunction "14_14") (pintype "bidirectional"))
      (node (ref "J4") (pin "P3") (pinfunction "CMD_P3") (pintype "bidirectional"))
      (node (ref "R7") (pin "1") (pinfunction "1_1") (pintype "passive"))
      (node (ref "TP7") (pin "TP") (pinfunction "TP_TP") (pintype "input"))
      (node (ref "U1") (pin "5") (pinfunction "DI(IO0)_5") (pintype "bidirectional"))
      (node (ref "U2") (pin "7") (pinfunction "IO7_7") (pintype "bidirectional"))
    )
    (net (code "21") (name "Net-(CHG_LED-PadC)") (class "Default")
      (node (ref "CHG_LED") (pin "C") (pinfunction "C_C") (pintype "passive"))
      (node (ref "R1_BAT") (pin "1") (pinfunction "1_1") (pintype "passive"))
    )
    (net (code "22") (name "Net-(D2-CATHODE)") (class "Default")
      (node (ref "C1_BAT1") (pin "1") (pinfunction "1_1") (pintype "passive"))
      (node (ref "D2") (pin "1") (pinfunction "CATHODE_1") (pintype "bidirectional"))
      (node (ref "IC4") (pin "1") (pinfunction "VIN_1") (pintype "bidirectional"))
      (node (ref "IC4") (pin "3") (pinfunction "CE_3") (pintype "bidirectional"))
      (node (ref "Q1") (pin "2") (pinfunction "S_2") (pintype "bidirectional"))
    )
    (net (code "23") (name "Net-(D3-A)") (class "Default")
      (node (ref "C4") (pin "1") (pinfunction "1_1") (pintype "passive"))
      (node (ref "D3") (pin "2") (pinfunction "A_2") (pintype "bidirectional"))
      (node (ref "D4") (pin "1") (pinfunction "K_1") (pintype "bidirectional"))
    )
    (net (code "24") (name "Net-(D7-CATHODE)") (class "Default")
      (node (ref "D7") (pin "1") (pinfunction "CATHODE_1") (pintype "bidirectional"))
      (node (ref "R_CAPACITOR") (pin "1") (pinfunction "1_1") (pintype "passive"))
    )
    (net (code "25") (name "Net-(EPD_C1-Pad2)") (class "Default")
      (node (ref "EPD_C1") (pin "2") (pinfunction "2_2") (pintype "passive"))
      (node (ref "J1") (pin "4") (pinfunction "4_4") (pintype "bidirectional"))
    )
    (net (code "26") (name "Net-(EPD_C2-Pad2)") (class "Default")
      (node (ref "EPD_C2") (pin "2") (pinfunction "2_2") (pintype "passive"))
      (node (ref "J1") (pin "5") (pinfunction "5_5") (pintype "bidirectional"))
    )
    (net (code "27") (name "Net-(EPD_C6-Pad2)") (class "Default")
      (node (ref "EPD_C6") (pin "2") (pinfunction "2_2") (pintype "passive"))
      (node (ref "J1") (pin "18") (pinfunction "18_18") (pintype "bidirectional"))
    )
    (net (code "28") (name "Net-(EPD_C7-Pad2)") (class "Default")
      (node (ref "EPD_C7") (pin "2") (pinfunction "2_2") (pintype "passive"))
      (node (ref "J1") (pin "19") (pinfunction "19_19") (pintype "bidirectional"))
    )
    (net (code "29") (name "Net-(EPD_C8-Pad2)") (class "Default")
      (node (ref "EPD_C8") (pin "2") (pinfunction "2_2") (pintype "passive"))
      (node (ref "J1") (pin "20") (pinfunction "20_20") (pintype "bidirectional"))
    )
    (net (code "30") (name "Net-(EPD_C10-Pad2)") (class "Default")
      (node (ref "EPD_C10") (pin "2") (pinfunction "2_2") (pintype "passive"))
      (node (ref "J1") (pin "22") (pinfunction "22_22") (pintype "bidirectional"))
    )
    (net (code "31") (name "Net-(EPD_C12-Pad2)") (class "Default")
      (node (ref "EPD_C12") (pin "2") (pinfunction "2_2") (pintype "passive"))
      (node (ref "J1") (pin "24") (pinfunction "24_24") (pintype "bidirectional"))
    )
    (net (code "32") (name "Net-(IC1-CT)") (class "Default")
      (node (ref "C_DELAY") (pin "1") (pinfunction "1_1") (pintype "passive"))
      (node (ref "IC1") (pin "5") (pinfunction "CT_5") (pintype "bidirectional"))
    )
    (net (code "33") (name "Net-(J2-PadA5)") (class "Default")
      (node (ref "J2") (pin "A5") (pinfunction "A5_A5") (pintype "bidirectional"))
      (node (ref "R2_USB1") (pin "2") (pinfunction "2_2") (pintype "passive"))
    )
    (net (code "34") (name "Net-(J2-PadB5)") (class "Default")
      (node (ref "J2") (pin "B5") (pinfunction "B5_B5") (pintype "bidirectional"))
      (node (ref "R2_USB") (pin "1") (pinfunction "1_1") (pintype "passive"))
    )
    (net (code "35") (name "Net-(MCP73831-PROG)") (class "Default")
      (node (ref "MCP73831") (pin "5") (pinfunction "PROG_5") (pintype "input"))
      (node (ref "R2_BAT") (pin "2") (pinfunction "2_2") (pintype "passive"))
    )
    (net (code "36") (name "Net-(MCP73831-STAT)") (class "Default")
      (node (ref "MCP73831") (pin "1") (pinfunction "STAT_1") (pintype "output"))
      (node (ref "R1_BAT") (pin "2") (pinfunction "2_2") (pintype "passive"))
    )
    (net (code "37") (name "PREVGH") (class "Default")
      (node (ref "D5") (pin "1") (pinfunction "K_1") (pintype "bidirectional"))
      (node (ref "EPD_C9") (pin "2") (pinfunction "2_2") (pintype "passive"))
      (node (ref "J1") (pin "21") (pinfunction "21_21") (pintype "bidirectional"))
    )
    (net (code "38") (name "PREVGL") (class "Default")
      (node (ref "D4") (pin "2") (pinfunction "A_2") (pintype "bidirectional"))
      (node (ref "EPD_C11") (pin "2") (pinfunction "2_2") (pintype "passive"))
      (node (ref "J1") (pin "23") (pinfunction "23_23") (pintype "bidirectional"))
    )
    (net (code "39") (name "RESE") (class "Default")
      (node (ref "J1") (pin "3") (pinfunction "3_3") (pintype "bidirectional"))
      (node (ref "Q3") (pin "2") (pinfunction "S_2") (pintype "bidirectional"))
      (node (ref "R3") (pin "2") (pinfunction "2_2") (pintype "passive"))
    )
    (net (code "40") (name "RESE'") (class "Default")
      (node (ref "R1") (pin "2") (pinfunction "2_2") (pintype "passive"))
      (node (ref "R3") (pin "1") (pinfunction "1_1") (pintype "passive"))
      (node (ref "SJ1") (pin "2") (pinfunction "2_2") (pintype "passive"))
    )
    (net (code "41") (name "RESET") (class "Default")
      (node (ref "C5") (pin "1") (pinfunction "1_1") (pintype "passive"))
      (node (ref "IC1") (pin "1") (pinfunction "VOUT_1") (pintype "bidirectional"))
      (node (ref "RESET_BUTTON") (pin "3") (pinfunction "3_3") (pintype "passive"))
      (node (ref "RESET_BUTTON") (pin "4") (pinfunction "4_4") (pintype "passive"))
      (node (ref "R_RESET") (pin "1") (pinfunction "1_1") (pintype "passive"))
      (node (ref "U2") (pin "3") (pinfunction "EN_3") (pintype "input"))
    )
    (net (code "42") (name "RTC_RST") (class "Default")
      (node (ref "U2") (pin "16") (pinfunction "IO18_16") (pintype "bidirectional"))
      (node (ref "U3") (pin "4") (pinfunction "~{RST}_4") (pintype "input"))
    )
    (net (code "43") (name "RX") (class "Default")
      (node (ref "TP2") (pin "TP") (pinfunction "TP_TP") (pintype "input"))
      (node (ref "U2") (pin "24") (pinfunction "RXD0/GPIO17_24") (pintype "bidirectional"))
    )
    (net (code "44") (name "SCK") (class "Default")
      (node (ref "D10") (pin "2") (pinfunction "2_2") (pintype "passive"))
      (node (ref "J1") (pin "13") (pinfunction "13_13") (pintype "bidirectional"))
      (node (ref "J4") (pin "P5") (pinfunction "CLK_P5") (pintype "bidirectional"))
      (node (ref "R6") (pin "1") (pinfunction "1_1") (pintype "passive"))
      (node (ref "TP8") (pin "TP") (pinfunction "TP_TP") (pintype "input"))
      (node (ref "U1") (pin "6") (pinfunction "CLK_6") (pintype "input"))
      (node (ref "U2") (pin "6") (pinfunction "IO6_6") (pintype "bidirectional"))
    )
    (net (code "45") (name "SCL") (class "Default")
      (node (ref "J3") (pin "4") (pinfunction "4_4") (pintype "passive"))
      (node (ref "R2_PINH") (pin "1") (pinfunction "1_1") (pintype "passive"))
      (node (ref "SENSOR2") (pin "4") (pinfunction "SCK_4") (pintype "input"))
      (node (ref "U2") (pin "20") (pinfunction "IO22_20") (pintype "bidirectional"))
      (node (ref "U3") (pin "16") (pinfunction "SCL_16") (pintype "input"))
      (node (ref "U4") (pin "7") (pinfunction "SCL_7") (pintype "input"))
    )
    (net (code "46") (name "SDA") (class "Default")
      (node (ref "J3") (pin "3") (pinfunction "3_3") (pintype "passive"))
      (node (ref "R1_PINH") (pin "1") (pinfunction "1_1") (pintype "passive"))
      (node (ref "SENSOR2") (pin "3") (pinfunction "SDI_3") (pintype "bidirectional"))
      (node (ref "U2") (pin "19") (pinfunction "IO21_19") (pintype "bidirectional"))
      (node (ref "U3") (pin "15") (pinfunction "SDA_15") (pintype "bidirectional"))
      (node (ref "U4") (pin "8") (pinfunction "SDA_8") (pintype "bidirectional"))
    )
    (net (code "47") (name "SRC") (class "Default")
      (node (ref "C4") (pin "2") (pinfunction "2_2") (pintype "passive"))
      (node (ref "D5") (pin "2") (pinfunction "A_2") (pintype "bidirectional"))
      (node (ref "L1") (pin "1") (pinfunction "1_1") (pintype "passive"))
      (node (ref "Q3") (pin "3") (pinfunction "D_3") (pintype "bidirectional"))
    )
    (net (code "48") (name "SS_SD") (class "Default")
      (node (ref "D6") (pin "2") (pinfunction "2_2") (pintype "passive"))
      (node (ref "J4") (pin "P2") (pinfunction "CD/DAT3_P2") (pintype "bidirectional"))
      (node (ref "R10") (pin "1") (pinfunction "1_1") (pintype "passive"))
      (node (ref "U2") (pin "4") (pinfunction "IO4_4") (pintype "bidirectional"))
    )
    (net (code "49") (name "TX") (class "Default")
      (node (ref "TP1") (pin "TP") (pinfunction "TP_TP") (pintype "input"))
      (node (ref "U2") (pin "25") (pinfunction "TXD0/GPIO16_25") (pintype "bidirectional"))
    )
    (net (code "50") (name "USB_D+") (class "Default")
      (node (ref "D1") (pin "1") (pinfunction "I/O1_1_1") (pintype "bidirectional"))
      (node (ref "U2") (pin "14") (pinfunction "IO13_14") (pintype "bidirectional"))
    )
    (net (code "51") (name "USB_D-") (class "Default")
      (node (ref "D1") (pin "3") (pinfunction "I/O2_1_3") (pintype "bidirectional"))
      (node (ref "U2") (pin "13") (pinfunction "IO12_13") (pintype "bidirectional"))
    )
    (net (code "52") (name "VBAT") (class "Default")
      (node (ref "C2_BAT") (pin "1") (pinfunction "1_1") (pintype "passive"))
      (node (ref "MCP73831") (pin "3") (pinfunction "VBAT_3") (pintype "power_in"))
      (node (ref "Q1") (pin "3") (pinfunction "D_3") (pintype "bidirectional"))
      (node (ref "TP3") (pin "TP") (pinfunction "TP_TP") (pintype "input"))
      (node (ref "U4") (pin "2") (pinfunction "CELL_2") (pintype "power_in"))
      (node (ref "U4") (pin "3") (pinfunction "VDD_3") (pintype "power_in"))
    )
    (net (code "53") (name "VBUS") (class "Default")
      (node (ref "C1_BAT") (pin "1") (pinfunction "1_1") (pintype "passive"))
      (node (ref "C4_USB") (pin "1") (pinfunction "1_1") (pintype "passive"))
      (node (ref "C5_USB") (pin "1") (pinfunction "1_1") (pintype "passive"))
      (node (ref "CHG_LED") (pin "A") (pinfunction "A_A") (pintype "passive"))
      (node (ref "D1") (pin "5") (pinfunction "VBUS_5") (pintype "bidirectional"))
      (node (ref "D2") (pin "2") (pinfunction "ANODE_2") (pintype "bidirectional"))
      (node (ref "MCP73831") (pin "4") (pinfunction "VIN_4") (pintype "power_in"))
      (node (ref "PFMF.050.1") (pin "2") (pinfunction "2_2") (pintype "passive"))
      (node (ref "Q1") (pin "1") (pinfunction "G_1") (pintype "bidirectional"))
      (node (ref "R1_PWRUSB") (pin "2") (pinfunction "2_2") (pintype "passive"))
      (node (ref "TP14") (pin "TP") (pinfunction "TP_TP") (pintype "input"))
    )
    (net (code "54") (name "VRTC") (class "Default")
      (node (ref "C10_SUPERCAP") (pin "2") (pinfunction "2_2") (pintype "passive"))
      (node (ref "C8") (pin "1") (pinfunction "1_1") (pintype "passive"))
      (node (ref "R_CAPACITOR") (pin "2") (pinfunction "2_2") (pintype "passive"))
      (node (ref "U3") (pin "14") (pinfunction "VBAT_14") (pintype "power_in"))
    )
    (net (code "55") (name "VUSB") (class "Default")
      (node (ref "J2") (pin "A4") (pinfunction "A4_A4") (pintype "bidirectional"))
      (node (ref "J2") (pin "A9") (pinfunction "A9_A9") (pintype "bidirectional"))
      (node (ref "J2") (pin "B4") (pinfunction "B4_B4") (pintype "bidirectional"))
      (node (ref "J2") (pin "B9") (pinfunction "B9_B9") (pintype "bidirectional"))
      (node (ref "PFMF.050.1") (pin "1") (pinfunction "1_1") (pintype "passive"))
    )
    (net (code "56") (name "unconnected-(IC1-NC-Pad4)") (class "Default")
      (node (ref "IC1") (pin "4") (pinfunction "NC_4") (pintype "no_connect"))
    )
    (net (code "57") (name "unconnected-(IC4-NC-Pad4)") (class "Default")
      (node (ref "IC4") (pin "4") (pinfunction "NC_4") (pintype "no_connect"))
    )
    (net (code "58") (name "unconnected-(J1-Pad1)") (class "Default")
      (node (ref "J1") (pin "1") (pinfunction "1_1") (pintype "bidirectional"))
    )
    (net (code "59") (name "unconnected-(J1-Pad6)") (class "Default")
      (node (ref "J1") (pin "6") (pinfunction "6_6") (pintype "bidirectional"))
    )
    (net (code "60") (name "unconnected-(J1-Pad7)") (class "Default")
      (node (ref "J1") (pin "7") (pinfunction "7_7") (pintype "bidirectional"))
    )
    (net (code "61") (name "unconnected-(J2-PadA8)") (class "Default")
      (node (ref "J2") (pin "A8") (pinfunction "A8_A8") (pintype "bidirectional"))
    )
    (net (code "62") (name "unconnected-(J2-PadB8)") (class "Default")
      (node (ref "J2") (pin "B8") (pinfunction "B8_B8") (pintype "bidirectional"))
    )
    (net (code "63") (name "unconnected-(J4-DAT1-PadP8)") (class "Default")
      (node (ref "J4") (pin "P8") (pinfunction "DAT1_P8") (pintype "bidirectional"))
    )
    (net (code "64") (name "unconnected-(J4-DAT2-PadP1)") (class "Default")
      (node (ref "J4") (pin "P1") (pinfunction "DAT2_P1") (pintype "bidirectional"))
    )
    (net (code "65") (name "unconnected-(J4-DETECTION_1-PadS1)") (class "Default")
      (node (ref "J4") (pin "S1") (pinfunction "DETECTION_1_S1") (pintype "bidirectional"))
    )
    (net (code "66") (name "unconnected-(J4-DETECTION_2-PadS2)") (class "Default")
      (node (ref "J4") (pin "S2") (pinfunction "DETECTION_2_S2") (pintype "bidirectional"))
    )
    (net (code "67") (name "unconnected-(U2-NC-Pad22)") (class "Default")
      (node (ref "U2") (pin "22") (pinfunction "NC_22") (pintype "no_connect"))
    )
    (net (code "68") (name "unconnected-(U4-~{ALERT}-Pad5)") (class "Default")
      (node (ref "U4") (pin "5") (pinfunction "~{ALERT}_5") (pintype "output"))
    )
  )
)
